# Data_Logger.net
KiCad netlist of a schematic drawn in Altium Designer
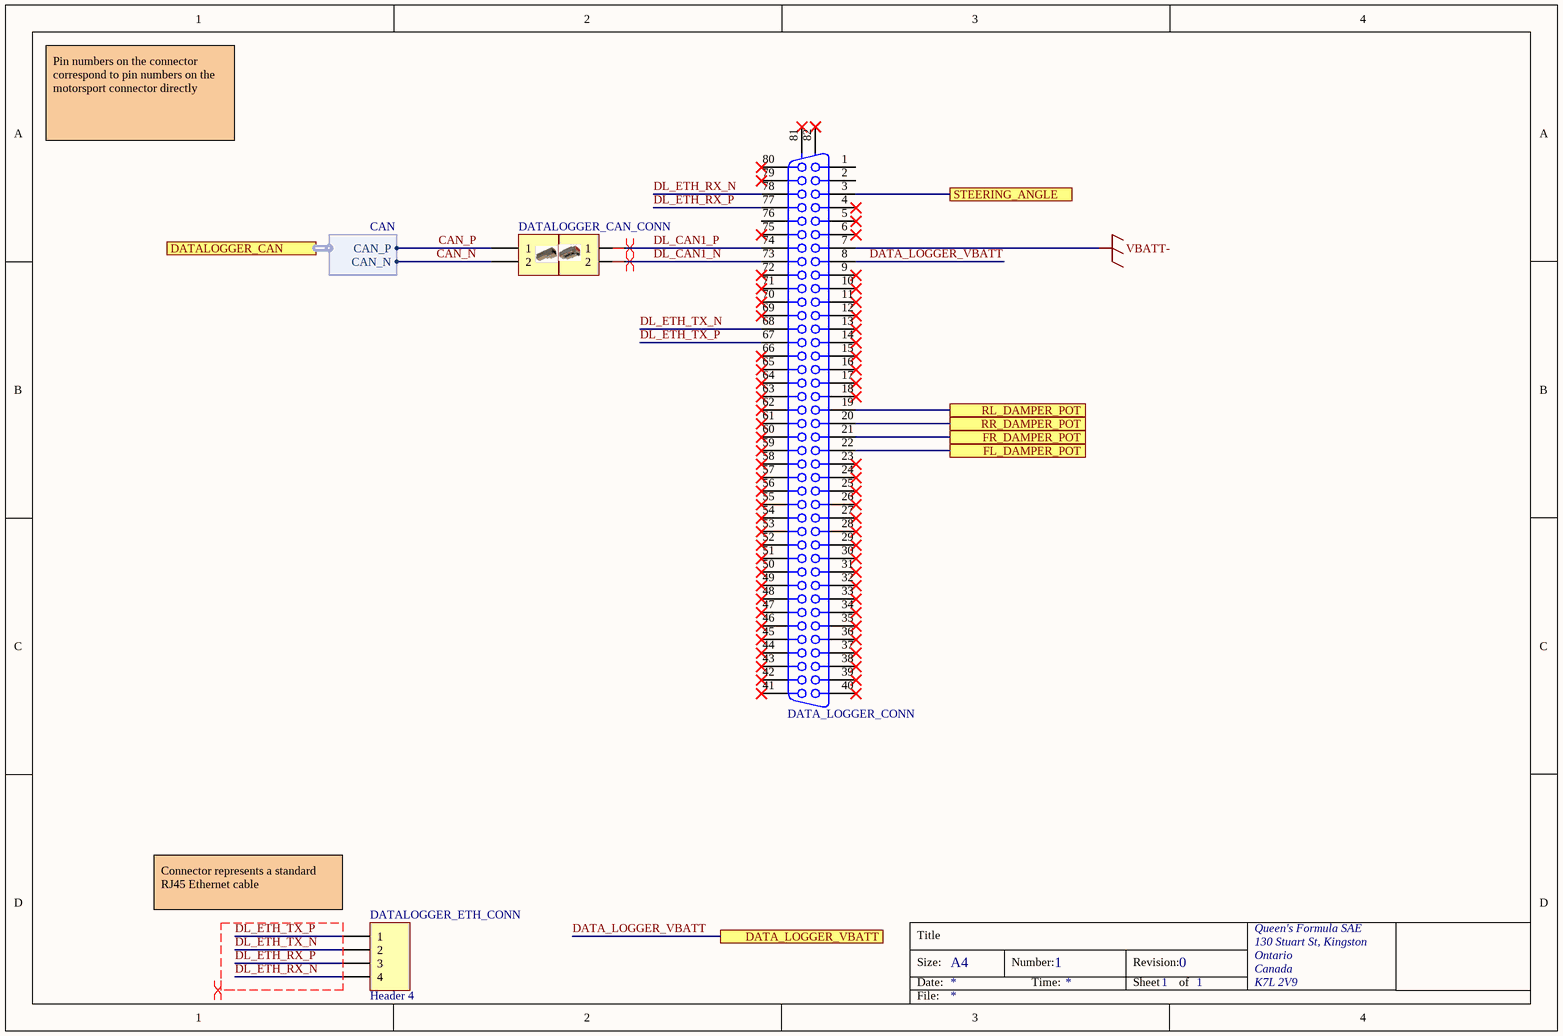
[diagram p0: Data Logger.SchDoc]

(export (version "E")
  (design (tool "Eeschema 10.0.6"))
  (components
    (comp (ref "DATALOGGER_CAN_CONN")
      (value "Header 2")
      (footprint "HDR1X2")
      (description "Header, 2-Pin")
      (fields (field (name "PUBLISHER") "Altium Limited"))
      (libsource (lib "") (part "Header 2_1"))
    )
    (comp (ref "DATALOGGER_ETH_CONN")
      (value "Header 4")
      (footprint "HDR1X4")
      (description "Header, 4-Pin")
      (fields (field (name "PUBLISHER") "Altium Limited"))
      (libsource (lib "Miscellaneous Connectors") (part "Header 4"))
    )
    (comp (ref "DATA_LOGGER_CAN_CONN")
      (value "Header 2")
      (footprint "HDR1X2")
      (description "Header, 2-Pin")
      (fields (field (name "PUBLISHER") "Altium Limited"))
      (libsource (lib "Miscellaneous Connectors") (part "Header 2"))
    )
    (comp (ref "DATA_LOGGER_CONN")
      (value "Connector 80")
      (footprint "CHAMP1.27-2V80")
      (description "Receptacle Header Assemby")
      (fields (field (name "PUBLISHER") "Altium Limited"))
      (libsource (lib "Miscellaneous Connectors") (part "Connector 80"))
    )
  )
  (nets
    (net (code "2") (name "/CAN_N") (class "Default")
      (node (ref "DATALOGGER_CAN_CONN") (pin "2") (pinfunction "2_2") (pintype "passive"))
    )
    (net (code "3") (name "/CAN_P") (class "Default")
      (node (ref "DATALOGGER_CAN_CONN") (pin "1") (pinfunction "1_1") (pintype "passive"))
    )
    (net (code "4") (name "/DATA_LOGGER_VBATT") (class "Default")
      (node (ref "DATA_LOGGER_CONN") (pin "8") (pinfunction "8_8") (pintype "passive"))
    )
    (net (code "5") (name "/DL_CAN1_N") (class "Default")
      (node (ref "DATA_LOGGER_CAN_CONN") (pin "2") (pinfunction "2_2") (pintype "passive"))
      (node (ref "DATA_LOGGER_CONN") (pin "73") (pinfunction "73_73") (pintype "passive"))
    )
    (net (code "6") (name "/DL_CAN1_P") (class "Default")
      (node (ref "DATA_LOGGER_CAN_CONN") (pin "1") (pinfunction "1_1") (pintype "passive"))
      (node (ref "DATA_LOGGER_CONN") (pin "74") (pinfunction "74_74") (pintype "passive"))
    )
    (net (code "7") (name "/DL_ETH_RX_N") (class "Default")
      (node (ref "DATALOGGER_ETH_CONN") (pin "4") (pinfunction "4_4") (pintype "passive"))
      (node (ref "DATA_LOGGER_CONN") (pin "78") (pinfunction "78_78") (pintype "passive"))
    )
    (net (code "8") (name "/DL_ETH_RX_P") (class "Default")
      (node (ref "DATALOGGER_ETH_CONN") (pin "3") (pinfunction "3_3") (pintype "passive"))
      (node (ref "DATA_LOGGER_CONN") (pin "77") (pinfunction "77_77") (pintype "passive"))
    )
    (net (code "9") (name "/DL_ETH_TX_N") (class "Default")
      (node (ref "DATALOGGER_ETH_CONN") (pin "2") (pinfunction "2_2") (pintype "passive"))
      (node (ref "DATA_LOGGER_CONN") (pin "68") (pinfunction "68_68") (pintype "passive"))
    )
    (net (code "10") (name "/DL_ETH_TX_P") (class "Default")
      (node (ref "DATALOGGER_ETH_CONN") (pin "1") (pinfunction "1_1") (pintype "passive"))
      (node (ref "DATA_LOGGER_CONN") (pin "67") (pinfunction "67_67") (pintype "passive"))
    )
    (net (code "11") (name "/FL_DAMPER_POT") (class "Default")
      (node (ref "DATA_LOGGER_CONN") (pin "22") (pinfunction "22_22") (pintype "passive"))
    )
    (net (code "12") (name "/FR_DAMPER_POT") (class "Default")
      (node (ref "DATA_LOGGER_CONN") (pin "21") (pinfunction "21_21") (pintype "passive"))
    )
    (net (code "13") (name "/RL_DAMPER_POT") (class "Default")
      (node (ref "DATA_LOGGER_CONN") (pin "19") (pinfunction "19_19") (pintype "passive"))
    )
    (net (code "14") (name "/RR_DAMPER_POT") (class "Default")
      (node (ref "DATA_LOGGER_CONN") (pin "20") (pinfunction "20_20") (pintype "passive"))
    )
    (net (code "15") (name "/STEERING_ANGLE") (class "Default")
      (node (ref "DATA_LOGGER_CONN") (pin "3") (pinfunction "3_3") (pintype "passive"))
    )
    (net (code "17") (name "VBATT-") (class "Default")
      (node (ref "DATA_LOGGER_CONN") (pin "7") (pinfunction "7_7") (pintype "passive"))
    )
    (net (code "18") (name "unconnected-(DATA_LOGGER_CONN-MH1-Pad81)") (class "Default")
      (node (ref "DATA_LOGGER_CONN") (pin "81") (pinfunction "MH1_81") (pintype "passive+no_connect"))
    )
    (net (code "19") (name "unconnected-(DATA_LOGGER_CONN-MH2-Pad82)") (class "Default")
      (node (ref "DATA_LOGGER_CONN") (pin "82") (pinfunction "MH2_82") (pintype "passive+no_connect"))
    )
    (net (code "20") (name "unconnected-(DATA_LOGGER_CONN-Pad1)") (class "Default")
      (node (ref "DATA_LOGGER_CONN") (pin "1") (pinfunction "1_1") (pintype "passive"))
    )
    (net (code "21") (name "unconnected-(DATA_LOGGER_CONN-Pad2)") (class "Default")
      (node (ref "DATA_LOGGER_CONN") (pin "2") (pinfunction "2_2") (pintype "passive"))
    )
    (net (code "22") (name "unconnected-(DATA_LOGGER_CONN-Pad4)") (class "Default")
      (node (ref "DATA_LOGGER_CONN") (pin "4") (pinfunction "4_4") (pintype "passive+no_connect"))
    )
    (net (code "23") (name "unconnected-(DATA_LOGGER_CONN-Pad5)") (class "Default")
      (node (ref "DATA_LOGGER_CONN") (pin "5") (pinfunction "5_5") (pintype "passive+no_connect"))
    )
    (net (code "24") (name "unconnected-(DATA_LOGGER_CONN-Pad6)") (class "Default")
      (node (ref "DATA_LOGGER_CONN") (pin "6") (pinfunction "6_6") (pintype "passive+no_connect"))
    )
    (net (code "25") (name "unconnected-(DATA_LOGGER_CONN-Pad9)") (class "Default")
      (node (ref "DATA_LOGGER_CONN") (pin "9") (pinfunction "9_9") (pintype "passive+no_connect"))
    )
    (net (code "26") (name "unconnected-(DATA_LOGGER_CONN-Pad10)") (class "Default")
      (node (ref "DATA_LOGGER_CONN") (pin "10") (pinfunction "10_10") (pintype "passive+no_connect"))
    )
    (net (code "27") (name "unconnected-(DATA_LOGGER_CONN-Pad11)") (class "Default")
      (node (ref "DATA_LOGGER_CONN") (pin "11") (pinfunction "11_11") (pintype "passive+no_connect"))
    )
    (net (code "28") (name "unconnected-(DATA_LOGGER_CONN-Pad12)") (class "Default")
      (node (ref "DATA_LOGGER_CONN") (pin "12") (pinfunction "12_12") (pintype "passive+no_connect"))
    )
    (net (code "29") (name "unconnected-(DATA_LOGGER_CONN-Pad13)") (class "Default")
      (node (ref "DATA_LOGGER_CONN") (pin "13") (pinfunction "13_13") (pintype "passive+no_connect"))
    )
    (net (code "30") (name "unconnected-(DATA_LOGGER_CONN-Pad14)") (class "Default")
      (node (ref "DATA_LOGGER_CONN") (pin "14") (pinfunction "14_14") (pintype "passive+no_connect"))
    )
    (net (code "31") (name "unconnected-(DATA_LOGGER_CONN-Pad15)") (class "Default")
      (node (ref "DATA_LOGGER_CONN") (pin "15") (pinfunction "15_15") (pintype "passive+no_connect"))
    )
    (net (code "32") (name "unconnected-(DATA_LOGGER_CONN-Pad16)") (class "Default")
      (node (ref "DATA_LOGGER_CONN") (pin "16") (pinfunction "16_16") (pintype "passive+no_connect"))
    )
    (net (code "33") (name "unconnected-(DATA_LOGGER_CONN-Pad17)") (class "Default")
      (node (ref "DATA_LOGGER_CONN") (pin "17") (pinfunction "17_17") (pintype "passive+no_connect"))
    )
    (net (code "34") (name "unconnected-(DATA_LOGGER_CONN-Pad18)") (class "Default")
      (node (ref "DATA_LOGGER_CONN") (pin "18") (pinfunction "18_18") (pintype "passive+no_connect"))
    )
    (net (code "35") (name "unconnected-(DATA_LOGGER_CONN-Pad23)") (class "Default")
      (node (ref "DATA_LOGGER_CONN") (pin "23") (pinfunction "23_23") (pintype "passive+no_connect"))
    )
    (net (code "36") (name "unconnected-(DATA_LOGGER_CONN-Pad24)") (class "Default")
      (node (ref "DATA_LOGGER_CONN") (pin "24") (pinfunction "24_24") (pintype "passive+no_connect"))
    )
    (net (code "37") (name "unconnected-(DATA_LOGGER_CONN-Pad25)") (class "Default")
      (node (ref "DATA_LOGGER_CONN") (pin "25") (pinfunction "25_25") (pintype "passive+no_connect"))
    )
    (net (code "38") (name "unconnected-(DATA_LOGGER_CONN-Pad26)") (class "Default")
      (node (ref "DATA_LOGGER_CONN") (pin "26") (pinfunction "26_26") (pintype "passive+no_connect"))
    )
    (net (code "39") (name "unconnected-(DATA_LOGGER_CONN-Pad27)") (class "Default")
      (node (ref "DATA_LOGGER_CONN") (pin "27") (pinfunction "27_27") (pintype "passive+no_connect"))
    )
    (net (code "40") (name "unconnected-(DATA_LOGGER_CONN-Pad28)") (class "Default")
      (node (ref "DATA_LOGGER_CONN") (pin "28") (pinfunction "28_28") (pintype "passive+no_connect"))
    )
    (net (code "41") (name "unconnected-(DATA_LOGGER_CONN-Pad29)") (class "Default")
      (node (ref "DATA_LOGGER_CONN") (pin "29") (pinfunction "29_29") (pintype "passive+no_connect"))
    )
    (net (code "42") (name "unconnected-(DATA_LOGGER_CONN-Pad30)") (class "Default")
      (node (ref "DATA_LOGGER_CONN") (pin "30") (pinfunction "30_30") (pintype "passive+no_connect"))
    )
    (net (code "43") (name "unconnected-(DATA_LOGGER_CONN-Pad31)") (class "Default")
      (node (ref "DATA_LOGGER_CONN") (pin "31") (pinfunction "31_31") (pintype "passive+no_connect"))
    )
    (net (code "44") (name "unconnected-(DATA_LOGGER_CONN-Pad32)") (class "Default")
      (node (ref "DATA_LOGGER_CONN") (pin "32") (pinfunction "32_32") (pintype "passive+no_connect"))
    )
    (net (code "45") (name "unconnected-(DATA_LOGGER_CONN-Pad33)") (class "Default")
      (node (ref "DATA_LOGGER_CONN") (pin "33") (pinfunction "33_33") (pintype "passive+no_connect"))
    )
    (net (code "46") (name "unconnected-(DATA_LOGGER_CONN-Pad34)") (class "Default")
      (node (ref "DATA_LOGGER_CONN") (pin "34") (pinfunction "34_34") (pintype "passive+no_connect"))
    )
    (net (code "47") (name "unconnected-(DATA_LOGGER_CONN-Pad35)") (class "Default")
      (node (ref "DATA_LOGGER_CONN") (pin "35") (pinfunction "35_35") (pintype "passive+no_connect"))
    )
    (net (code "48") (name "unconnected-(DATA_LOGGER_CONN-Pad36)") (class "Default")
      (node (ref "DATA_LOGGER_CONN") (pin "36") (pinfunction "36_36") (pintype "passive+no_connect"))
    )
    (net (code "49") (name "unconnected-(DATA_LOGGER_CONN-Pad37)") (class "Default")
      (node (ref "DATA_LOGGER_CONN") (pin "37") (pinfunction "37_37") (pintype "passive+no_connect"))
    )
    (net (code "50") (name "unconnected-(DATA_LOGGER_CONN-Pad38)") (class "Default")
      (node (ref "DATA_LOGGER_CONN") (pin "38") (pinfunction "38_38") (pintype "passive+no_connect"))
    )
    (net (code "51") (name "unconnected-(DATA_LOGGER_CONN-Pad39)") (class "Default")
      (node (ref "DATA_LOGGER_CONN") (pin "39") (pinfunction "39_39") (pintype "passive+no_connect"))
    )
    (net (code "52") (name "unconnected-(DATA_LOGGER_CONN-Pad40)") (class "Default")
      (node (ref "DATA_LOGGER_CONN") (pin "40") (pinfunction "40_40") (pintype "passive+no_connect"))
    )
    (net (code "53") (name "unconnected-(DATA_LOGGER_CONN-Pad41)") (class "Default")
      (node (ref "DATA_LOGGER_CONN") (pin "41") (pinfunction "41_41") (pintype "passive+no_connect"))
    )
    (net (code "54") (name "unconnected-(DATA_LOGGER_CONN-Pad42)") (class "Default")
      (node (ref "DATA_LOGGER_CONN") (pin "42") (pinfunction "42_42") (pintype "passive+no_connect"))
    )
    (net (code "55") (name "unconnected-(DATA_LOGGER_CONN-Pad43)") (class "Default")
      (node (ref "DATA_LOGGER_CONN") (pin "43") (pinfunction "43_43") (pintype "passive+no_connect"))
    )
    (net (code "56") (name "unconnected-(DATA_LOGGER_CONN-Pad44)") (class "Default")
      (node (ref "DATA_LOGGER_CONN") (pin "44") (pinfunction "44_44") (pintype "passive+no_connect"))
    )
    (net (code "57") (name "unconnected-(DATA_LOGGER_CONN-Pad45)") (class "Default")
      (node (ref "DATA_LOGGER_CONN") (pin "45") (pinfunction "45_45") (pintype "passive+no_connect"))
    )
    (net (code "58") (name "unconnected-(DATA_LOGGER_CONN-Pad46)") (class "Default")
      (node (ref "DATA_LOGGER_CONN") (pin "46") (pinfunction "46_46") (pintype "passive+no_connect"))
    )
    (net (code "59") (name "unconnected-(DATA_LOGGER_CONN-Pad47)") (class "Default")
      (node (ref "DATA_LOGGER_CONN") (pin "47") (pinfunction "47_47") (pintype "passive+no_connect"))
    )
    (net (code "60") (name "unconnected-(DATA_LOGGER_CONN-Pad48)") (class "Default")
      (node (ref "DATA_LOGGER_CONN") (pin "48") (pinfunction "48_48") (pintype "passive+no_connect"))
    )
    (net (code "61") (name "unconnected-(DATA_LOGGER_CONN-Pad49)") (class "Default")
      (node (ref "DATA_LOGGER_CONN") (pin "49") (pinfunction "49_49") (pintype "passive+no_connect"))
    )
    (net (code "62") (name "unconnected-(DATA_LOGGER_CONN-Pad50)") (class "Default")
      (node (ref "DATA_LOGGER_CONN") (pin "50") (pinfunction "50_50") (pintype "passive+no_connect"))
    )
    (net (code "63") (name "unconnected-(DATA_LOGGER_CONN-Pad51)") (class "Default")
      (node (ref "DATA_LOGGER_CONN") (pin "51") (pinfunction "51_51") (pintype "passive+no_connect"))
    )
    (net (code "64") (name "unconnected-(DATA_LOGGER_CONN-Pad52)") (class "Default")
      (node (ref "DATA_LOGGER_CONN") (pin "52") (pinfunction "52_52") (pintype "passive+no_connect"))
    )
    (net (code "65") (name "unconnected-(DATA_LOGGER_CONN-Pad53)") (class "Default")
      (node (ref "DATA_LOGGER_CONN") (pin "53") (pinfunction "53_53") (pintype "passive+no_connect"))
    )
    (net (code "66") (name "unconnected-(DATA_LOGGER_CONN-Pad54)") (class "Default")
      (node (ref "DATA_LOGGER_CONN") (pin "54") (pinfunction "54_54") (pintype "passive+no_connect"))
    )
    (net (code "67") (name "unconnected-(DATA_LOGGER_CONN-Pad55)") (class "Default")
      (node (ref "DATA_LOGGER_CONN") (pin "55") (pinfunction "55_55") (pintype "passive+no_connect"))
    )
    (net (code "68") (name "unconnected-(DATA_LOGGER_CONN-Pad56)") (class "Default")
      (node (ref "DATA_LOGGER_CONN") (pin "56") (pinfunction "56_56") (pintype "passive+no_connect"))
    )
    (net (code "69") (name "unconnected-(DATA_LOGGER_CONN-Pad57)") (class "Default")
      (node (ref "DATA_LOGGER_CONN") (pin "57") (pinfunction "57_57") (pintype "passive+no_connect"))
    )
    (net (code "70") (name "unconnected-(DATA_LOGGER_CONN-Pad58)") (class "Default")
      (node (ref "DATA_LOGGER_CONN") (pin "58") (pinfunction "58_58") (pintype "passive+no_connect"))
    )
    (net (code "71") (name "unconnected-(DATA_LOGGER_CONN-Pad59)") (class "Default")
      (node (ref "DATA_LOGGER_CONN") (pin "59") (pinfunction "59_59") (pintype "passive+no_connect"))
    )
    (net (code "72") (name "unconnected-(DATA_LOGGER_CONN-Pad60)") (class "Default")
      (node (ref "DATA_LOGGER_CONN") (pin "60") (pinfunction "60_60") (pintype "passive+no_connect"))
    )
    (net (code "73") (name "unconnected-(DATA_LOGGER_CONN-Pad61)") (class "Default")
      (node (ref "DATA_LOGGER_CONN") (pin "61") (pinfunction "61_61") (pintype "passive+no_connect"))
    )
    (net (code "74") (name "unconnected-(DATA_LOGGER_CONN-Pad62)") (class "Default")
      (node (ref "DATA_LOGGER_CONN") (pin "62") (pinfunction "62_62") (pintype "passive+no_connect"))
    )
    (net (code "75") (name "unconnected-(DATA_LOGGER_CONN-Pad63)") (class "Default")
      (node (ref "DATA_LOGGER_CONN") (pin "63") (pinfunction "63_63") (pintype "passive+no_connect"))
    )
    (net (code "76") (name "unconnected-(DATA_LOGGER_CONN-Pad64)") (class "Default")
      (node (ref "DATA_LOGGER_CONN") (pin "64") (pinfunction "64_64") (pintype "passive+no_connect"))
    )
    (net (code "77") (name "unconnected-(DATA_LOGGER_CONN-Pad65)") (class "Default")
      (node (ref "DATA_LOGGER_CONN") (pin "65") (pinfunction "65_65") (pintype "passive+no_connect"))
    )
    (net (code "78") (name "unconnected-(DATA_LOGGER_CONN-Pad66)") (class "Default")
      (node (ref "DATA_LOGGER_CONN") (pin "66") (pinfunction "66_66") (pintype "passive+no_connect"))
    )
    (net (code "79") (name "unconnected-(DATA_LOGGER_CONN-Pad69)") (class "Default")
      (node (ref "DATA_LOGGER_CONN") (pin "69") (pinfunction "69_69") (pintype "passive+no_connect"))
    )
    (net (code "80") (name "unconnected-(DATA_LOGGER_CONN-Pad70)") (class "Default")
      (node (ref "DATA_LOGGER_CONN") (pin "70") (pinfunction "70_70") (pintype "passive+no_connect"))
    )
    (net (code "81") (name "unconnected-(DATA_LOGGER_CONN-Pad71)") (class "Default")
      (node (ref "DATA_LOGGER_CONN") (pin "71") (pinfunction "71_71") (pintype "passive+no_connect"))
    )
    (net (code "82") (name "unconnected-(DATA_LOGGER_CONN-Pad72)") (class "Default")
      (node (ref "DATA_LOGGER_CONN") (pin "72") (pinfunction "72_72") (pintype "passive+no_connect"))
    )
    (net (code "83") (name "unconnected-(DATA_LOGGER_CONN-Pad75)") (class "Default")
      (node (ref "DATA_LOGGER_CONN") (pin "75") (pinfunction "75_75") (pintype "passive+no_connect"))
    )
    (net (code "84") (name "unconnected-(DATA_LOGGER_CONN-Pad76)") (class "Default")
      (node (ref "DATA_LOGGER_CONN") (pin "76") (pinfunction "76_76") (pintype "passive"))
    )
    (net (code "85") (name "unconnected-(DATA_LOGGER_CONN-Pad79)") (class "Default")
      (node (ref "DATA_LOGGER_CONN") (pin "79") (pinfunction "79_79") (pintype "passive+no_connect"))
    )
    (net (code "86") (name "unconnected-(DATA_LOGGER_CONN-Pad80)") (class "Default")
      (node (ref "DATA_LOGGER_CONN") (pin "80") (pinfunction "80_80") (pintype "passive+no_connect"))
    )
  )
)
